# Schematics.net
KiCad netlist of a schematic drawn in Altium Designer
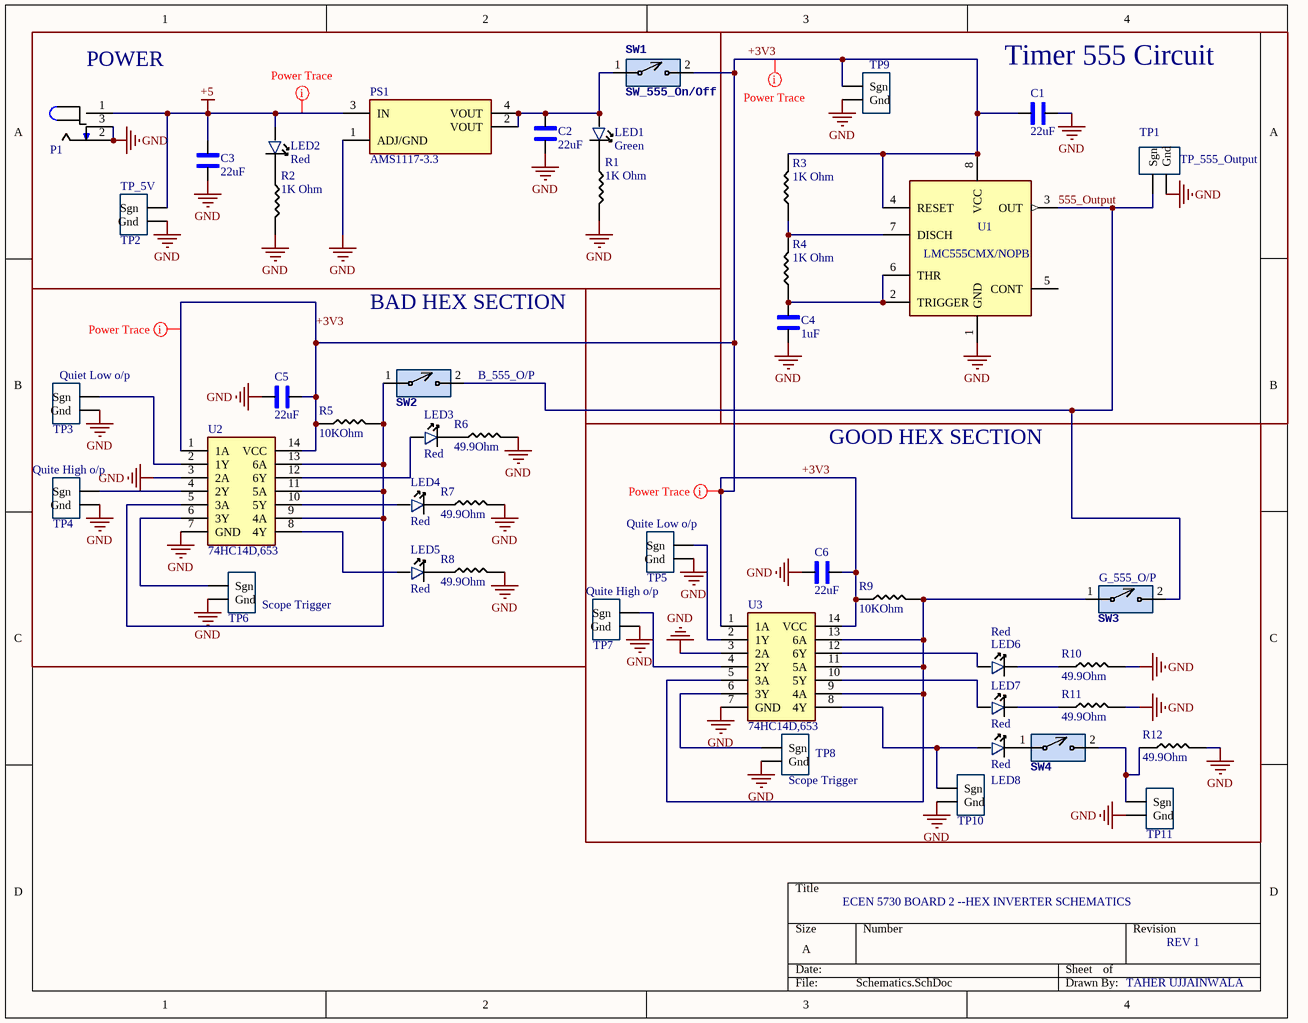
[diagram p0: Schematics.SchDoc]

(export (version "E")
  (design (tool "Eeschema 10.0.6"))
  (components
    (comp (ref "C1")
      (value "22uF")
      (footprint "0805_Passive_Capaciitor")
      (description "MULTILAYER CERAMIC CAPACITORS MLCC - SMD/SMT 22UF 25V 0805 ROHS")
      (fields (field (name "MFR PART #") "CL21A226MAQNNNE") (field (name "LCSC PART#") "C45783"))
      (libsource (lib "ECEN5730Lib_JLC_2021_08") (part "C_22uF_0805"))
    )
    (comp (ref "C2")
      (value "22uF")
      (footprint "0805_Passive_Capaciitor")
      (description "MULTILAYER CERAMIC CAPACITORS MLCC - SMD/SMT 22UF 25V 0805 ROHS")
      (fields (field (name "MFR PART #") "CL21A226MAQNNNE") (field (name "LCSC PART#") "C45783"))
      (libsource (lib "ECEN5730Lib_JLC_2021_08") (part "C_22uF_0805"))
    )
    (comp (ref "C3")
      (value "22uF")
      (footprint "0805_Passive_Capaciitor")
      (description "MULTILAYER CERAMIC CAPACITORS MLCC - SMD/SMT 22UF 25V 0805 ROHS")
      (fields (field (name "MFR PART #") "CL21A226MAQNNNE") (field (name "LCSC PART#") "C45783"))
      (libsource (lib "ECEN5730Lib_JLC_2021_08") (part "C_22uF_0805"))
    )
    (comp (ref "C4")
      (value "1uF")
      (footprint "0402_Passive_Capacitor")
      (description "MULTILAYER CERAMIC CAPACITORS MLCC - SMD/SMT 1UF 25V 0402 ROHS")
      (fields (field (name "MFR PART #") "CL05A105KA5NQNC") (field (name "LCSC PART#") "C52923"))
      (libsource (lib "ECEN5730Lib_JLC_2021_08") (part "C_1uF_0402"))
    )
    (comp (ref "C5")
      (value "22uF")
      (footprint "0805_Passive_Capaciitor")
      (description "MULTILAYER CERAMIC CAPACITORS MLCC - SMD/SMT 22UF 25V 0805 ROHS")
      (fields (field (name "MFR PART #") "CL21A226MAQNNNE") (field (name "LCSC PART#") "C45783"))
      (libsource (lib "ECEN5730Lib_JLC_2021_08") (part "C_22uF_0805"))
    )
    (comp (ref "C6")
      (value "22uF")
      (footprint "0805_Passive_Capaciitor")
      (description "MULTILAYER CERAMIC CAPACITORS MLCC - SMD/SMT 22UF 25V 0805 ROHS")
      (fields (field (name "MFR PART #") "CL21A226MAQNNNE") (field (name "LCSC PART#") "C45783"))
      (libsource (lib "ECEN5730Lib_JLC_2021_08") (part "C_22uF_0805"))
    )
    (comp (ref "LED1")
      (value "Green")
      (footprint "LED_0603")
      (description "LIGHT EMITTING DIODES (LED) GREEN 520~535NM 112~258MCD@20MA TOP VIEW 0603 ROHS")
      (fields (field (name "MFR PART #") "19-217/GHC-YR1S2/3T") (field (name "LCSC PART#") "C72043"))
      (libsource (lib "ECEN5730Lib_JLC_2021_08") (part "LED_GREEN_0603"))
    )
    (comp (ref "LED2")
      (value "Red")
      (footprint "LED_0603")
      (description "LIGHT EMITTING DIODES (LED) RED 520~625NM 90~100MCD@20MA TOP VIEW 0603 ROHS")
      (fields (field (name "MFR PART #") "KT-0603R") (field (name "LCSC PART#") "C2286"))
      (libsource (lib "ECEN5730Lib_JLC_2021_08") (part "LED_RED_0603"))
    )
    (comp (ref "LED3")
      (value "Red")
      (footprint "LED_0603")
      (description "LIGHT EMITTING DIODES (LED) RED 520~625NM 90~100MCD@20MA TOP VIEW 0603 ROHS")
      (fields (field (name "MFR PART #") "KT-0603R") (field (name "LCSC PART#") "C2286"))
      (libsource (lib "ECEN5730Lib_JLC_2021_08") (part "LED_RED_0603"))
    )
    (comp (ref "LED4")
      (value "Red")
      (footprint "LED_0603")
      (description "LIGHT EMITTING DIODES (LED) RED 520~625NM 90~100MCD@20MA TOP VIEW 0603 ROHS")
      (fields (field (name "MFR PART #") "KT-0603R") (field (name "LCSC PART#") "C2286"))
      (libsource (lib "ECEN5730Lib_JLC_2021_08") (part "LED_RED_0603"))
    )
    (comp (ref "LED5")
      (value "Red")
      (footprint "LED_0603")
      (description "LIGHT EMITTING DIODES (LED) RED 520~625NM 90~100MCD@20MA TOP VIEW 0603 ROHS")
      (fields (field (name "MFR PART #") "KT-0603R") (field (name "LCSC PART#") "C2286"))
      (libsource (lib "ECEN5730Lib_JLC_2021_08") (part "LED_RED_0603"))
    )
    (comp (ref "LED6")
      (value "Red")
      (footprint "LED_0603")
      (description "LIGHT EMITTING DIODES (LED) RED 520~625NM 90~100MCD@20MA TOP VIEW 0603 ROHS")
      (fields (field (name "MFR PART #") "KT-0603R") (field (name "LCSC PART#") "C2286"))
      (libsource (lib "ECEN5730Lib_JLC_2021_08") (part "LED_RED_0603"))
    )
    (comp (ref "LED7")
      (value "Red")
      (footprint "LED_0603")
      (description "LIGHT EMITTING DIODES (LED) RED 520~625NM 90~100MCD@20MA TOP VIEW 0603 ROHS")
      (fields (field (name "MFR PART #") "KT-0603R") (field (name "LCSC PART#") "C2286"))
      (libsource (lib "ECEN5730Lib_JLC_2021_08") (part "LED_RED_0603"))
    )
    (comp (ref "LED8")
      (value "Red")
      (footprint "LED_0603")
      (description "LIGHT EMITTING DIODES (LED) RED 520~625NM 90~100MCD@20MA TOP VIEW 0603 ROHS")
      (fields (field (name "MFR PART #") "KT-0603R") (field (name "LCSC PART#") "C2286"))
      (libsource (lib "ECEN5730Lib_JLC_2021_08") (part "LED_RED_0603"))
    )
    (comp (ref "P1")
      (value "Power Jack")
      (footprint "Power_Jack")
      (description "Power Barrel Connector Jack 2.10mm ID (0.083\"), 5.50mm OD (0.217\") Through Hole, Right Angle")
      (fields (field (name "DIGIKEY PART") "CP-102A-ND") (field (name "LCSC PART#") "C136744"))
      (libsource (lib "ECEN5730Lib_JLC_2021_08") (part "P_Power Jack"))
    )
    (comp (ref "PS1")
      (value "AMS1117-3.3")
      (footprint "LDO")
      (description "LOW DROPOUT REGULATORS(LDO) POSITIVE FIXED 1.3V @ 800MA 15V 3.3V 1A SOT-223 ROHS")
      (fields (field (name "LCSC PART#") "C6186"))
      (libsource (lib "ECEN5730Lib_JLC_2021_08") (part "PS_AMS_LDO_3v3"))
    )
    (comp (ref "R1")
      (value "1K Ohm")
      (footprint "0805_Passive_Resistor")
      (description "CHIP RESISTOR - SURFACE MOUNT 1KOHMS ±1% 1/8W 0805 ROHS")
      (fields (field (name "LCSC PART#") "C17513") (field (name "MFR PART #") "0805W8F1001T5E"))
      (libsource (lib "ECEN5730Lib_JLC_2021_08") (part "R_1K_0805"))
    )
    (comp (ref "R2")
      (value "1K Ohm")
      (footprint "0805_Passive_Resistor")
      (description "CHIP RESISTOR - SURFACE MOUNT 1KOHMS ±1% 1/8W 0805 ROHS")
      (fields (field (name "LCSC PART#") "C17513") (field (name "MFR PART #") "0805W8F1001T5E"))
      (libsource (lib "ECEN5730Lib_JLC_2021_08") (part "R_1K_0805"))
    )
    (comp (ref "R3")
      (value "1K Ohm")
      (footprint "0805_Passive_Resistor")
      (description "CHIP RESISTOR - SURFACE MOUNT 1KOHMS ±1% 1/8W 0805 ROHS")
      (fields (field (name "LCSC PART#") "C17513") (field (name "MFR PART #") "0805W8F1001T5E"))
      (libsource (lib "ECEN5730Lib_JLC_2021_08") (part "R_1K_0805"))
    )
    (comp (ref "R4")
      (value "1K Ohm")
      (footprint "0805_Passive_Resistor")
      (description "CHIP RESISTOR - SURFACE MOUNT 1KOHMS ±1% 1/8W 0805 ROHS")
      (fields (field (name "LCSC PART#") "C17513") (field (name "MFR PART #") "0805W8F1001T5E"))
      (libsource (lib "ECEN5730Lib_JLC_2021_08") (part "R_1K_0805"))
    )
    (comp (ref "R5")
      (value "10KOhm")
      (footprint "0402_Passive_Resistor")
      (description "CHIP RESISTOR - SURFACE MOUNT 10KOHMS ±1% 1/16W 0402 ROHS")
      (fields (field (name "MFR PART #") "0402WGF1002TCE") (field (name "LCSC PART#") "C25744"))
      (libsource (lib "ECEN5730Lib_JLC_2021_08") (part "R_10KOhm_0402"))
    )
    (comp (ref "R6")
      (value "49.9Ohm")
      (footprint "0402_Passive_Resistor")
      (description "CHIP RESISTOR - SURFACE MOUNT 49.9OHMS ±1% 1/16W 0402 ROHS")
      (fields (field (name "MFR PART #") "0402WGF499JTCE") (field (name "LCSC PART#") "C25120"))
      (libsource (lib "ECEN5730Lib_JLC_2021_08") (part "R_50Ohm_0402"))
    )
    (comp (ref "R7")
      (value "49.9Ohm")
      (footprint "0402_Passive_Resistor")
      (description "CHIP RESISTOR - SURFACE MOUNT 49.9OHMS ±1% 1/16W 0402 ROHS")
      (fields (field (name "MFR PART #") "0402WGF499JTCE") (field (name "LCSC PART#") "C25120"))
      (libsource (lib "ECEN5730Lib_JLC_2021_08") (part "R_50Ohm_0402"))
    )
    (comp (ref "R8")
      (value "49.9Ohm")
      (footprint "0402_Passive_Resistor")
      (description "CHIP RESISTOR - SURFACE MOUNT 49.9OHMS ±1% 1/16W 0402 ROHS")
      (fields (field (name "MFR PART #") "0402WGF499JTCE") (field (name "LCSC PART#") "C25120"))
      (libsource (lib "ECEN5730Lib_JLC_2021_08") (part "R_50Ohm_0402"))
    )
    (comp (ref "R9")
      (value "10KOhm")
      (footprint "0402_Passive_Resistor")
      (description "CHIP RESISTOR - SURFACE MOUNT 10KOHMS ±1% 1/16W 0402 ROHS")
      (fields (field (name "MFR PART #") "0402WGF1002TCE") (field (name "LCSC PART#") "C25744"))
      (libsource (lib "ECEN5730Lib_JLC_2021_08") (part "R_10KOhm_0402"))
    )
    (comp (ref "R10")
      (value "49.9Ohm")
      (footprint "0402_Passive_Resistor")
      (description "CHIP RESISTOR - SURFACE MOUNT 49.9OHMS ±1% 1/16W 0402 ROHS")
      (fields (field (name "MFR PART #") "0402WGF499JTCE") (field (name "LCSC PART#") "C25120"))
      (libsource (lib "ECEN5730Lib_JLC_2021_08") (part "R_50Ohm_0402"))
    )
    (comp (ref "R11")
      (value "49.9Ohm")
      (footprint "0402_Passive_Resistor")
      (description "CHIP RESISTOR - SURFACE MOUNT 49.9OHMS ±1% 1/16W 0402 ROHS")
      (fields (field (name "MFR PART #") "0402WGF499JTCE") (field (name "LCSC PART#") "C25120"))
      (libsource (lib "ECEN5730Lib_JLC_2021_08") (part "R_50Ohm_0402"))
    )
    (comp (ref "R12")
      (value "49.9Ohm")
      (footprint "0402_Passive_Resistor")
      (description "CHIP RESISTOR - SURFACE MOUNT 49.9OHMS ±1% 1/16W 0402 ROHS")
      (fields (field (name "MFR PART #") "0402WGF499JTCE") (field (name "LCSC PART#") "C25120"))
      (libsource (lib "ECEN5730Lib_JLC_2021_08") (part "R_50Ohm_0402"))
    )
    (comp (ref "SW1")
      (value "SW_555_On/Off")
      (footprint "2Pin-Header-Conn")
      (description "2Pin Header")
      (fields (field (name "LCSC PART#") "C124375"))
      (libsource (lib "ECEN5730Lib_JLC_2021_08") (part "SW_2Pin_100mil_Switch"))
    )
    (comp (ref "SW2")
      (value "SW_2Pin_100mil_Switch")
      (footprint "2Pin-Header-Conn")
      (description "2Pin Header")
      (fields (field (name "LCSC PART#") "C124375"))
      (libsource (lib "ECEN5730Lib_JLC_2021_08") (part "SW_2Pin_100mil_Switch"))
    )
    (comp (ref "SW3")
      (value "SW_2Pin_100mil_Switch")
      (footprint "2Pin-Header-Conn")
      (description "2Pin Header")
      (fields (field (name "LCSC PART#") "C124375"))
      (libsource (lib "ECEN5730Lib_JLC_2021_08") (part "SW_2Pin_100mil_Switch"))
    )
    (comp (ref "SW4")
      (value "SW_2Pin_100mil_Switch")
      (footprint "2Pin-Header-Conn")
      (description "2Pin Header")
      (fields (field (name "LCSC PART#") "C124375"))
      (libsource (lib "ECEN5730Lib_JLC_2021_08") (part "SW_2Pin_100mil_Switch"))
    )
    (comp (ref "TP1")
      (value "TP_555_Output")
      (footprint "TP10x_Probe")
      (description "Test Point 300 mil centers")
      (libsource (lib "") (part "TP_10x_Probe_2"))
    )
    (comp (ref "TP2")
      (value "TP_5V")
      (footprint "TP10x_Probe")
      (description "Test Point 300 mil centers")
      (libsource (lib "ECEN5730Lib_Manual_2021_08") (part "TP_10x_Probe"))
    )
    (comp (ref "TP3")
      (value "10x Probe TP")
      (footprint "TP10x_Probe")
      (description "Test Point 300 mil centers")
      (libsource (lib "ECEN5730Lib_Manual_2021_08") (part "TP_10x_Probe"))
    )
    (comp (ref "TP4")
      (value "10x Probe TP")
      (footprint "TP10x_Probe")
      (description "Test Point 300 mil centers")
      (libsource (lib "ECEN5730Lib_Manual_2021_08") (part "TP_10x_Probe"))
    )
    (comp (ref "TP5")
      (value "10x Probe TP")
      (footprint "TP10x_Probe")
      (description "Test Point 300 mil centers")
      (libsource (lib "ECEN5730Lib_Manual_2021_08") (part "TP_10x_Probe"))
    )
    (comp (ref "TP6")
      (value "10x Probe TP")
      (footprint "TP10x_Probe")
      (description "Test Point 300 mil centers")
      (libsource (lib "") (part "TP_10x_Probe_1"))
    )
    (comp (ref "TP7")
      (value "10x Probe TP")
      (footprint "TP10x_Probe")
      (description "Test Point 300 mil centers")
      (libsource (lib "ECEN5730Lib_Manual_2021_08") (part "TP_10x_Probe"))
    )
    (comp (ref "TP8")
      (value "10x Probe TP")
      (footprint "TP10x_Probe")
      (description "Test Point 300 mil centers")
      (libsource (lib "") (part "TP_10x_Probe_1"))
    )
    (comp (ref "TP9")
      (value "10x Probe TP")
      (footprint "TP10x_Probe")
      (description "Test Point 300 mil centers")
      (libsource (lib "") (part "TP_10x_Probe_1"))
    )
    (comp (ref "TP10")
      (value "10x Probe TP")
      (footprint "TP10x_Probe")
      (description "Test Point 300 mil centers")
      (libsource (lib "") (part "TP_10x_Probe_1"))
    )
    (comp (ref "TP11")
      (value "10x Probe TP")
      (footprint "TP10x_Probe")
      (description "Test Point 300 mil centers")
      (libsource (lib "") (part "TP_10x_Probe_1"))
    )
    (comp (ref "U1")
      (value "LMC555CMX/NOPB")
      (footprint "TS555IDTTR")
      (description "555 Type, Timer/Oscillator _Single_ IC 3MHz 8-SO")
      (fields (field (name "LCSC PART#") "C90760"))
      (libsource (lib "ECEN5730Lib_JLC_2021_08") (part "U_555_Fast"))
    )
    (comp (ref "U2")
      (value "74HC14D,653")
      (footprint "HEX_74AC14")
      (description "Inverter IC 6 Channel Schmitt Trigger 14-SOIC")
      (fields (field (name "LCSC PART#") "C5605"))
      (libsource (lib "ECEN5730Lib_JLC_2021_08") (part "U_7414_HC_Hex"))
    )
    (comp (ref "U3")
      (value "74HC14D,653")
      (footprint "HEX_74AC14")
      (description "Inverter IC 6 Channel Schmitt Trigger 14-SOIC")
      (fields (field (name "LCSC PART#") "C5605"))
      (libsource (lib "ECEN5730Lib_JLC_2021_08") (part "U_7414_HC_Hex"))
    )
  )
  (nets
    (net (code "1") (name "+5") (class "Default")
      (node (ref "C3") (pin "2") (pinfunction "2_2") (pintype "passive"))
      (node (ref "LED2") (pin "1") (pinfunction "1_1") (pintype "passive"))
      (node (ref "P1") (pin "1") (pinfunction "1_1") (pintype "power_in"))
      (node (ref "PS1") (pin "3") (pinfunction "IN_3") (pintype "power_in"))
      (node (ref "TP2") (pin "1") (pinfunction "Sgn_1") (pintype "passive"))
    )
    (net (code "2") (name "/+3V3") (class "Default")
      (node (ref "C1") (pin "1") (pinfunction "1_1") (pintype "passive"))
      (node (ref "C5") (pin "1") (pinfunction "1_1") (pintype "passive"))
      (node (ref "C6") (pin "1") (pinfunction "1_1") (pintype "passive"))
      (node (ref "R3") (pin "2") (pinfunction "2_2") (pintype "passive"))
      (node (ref "R5") (pin "1") (pinfunction "1_1") (pintype "passive"))
      (node (ref "R9") (pin "1") (pinfunction "1_1") (pintype "passive"))
      (node (ref "SW1") (pin "2") (pinfunction "2_2") (pintype "passive"))
      (node (ref "TP9") (pin "1") (pinfunction "Sgn_1") (pintype "passive"))
      (node (ref "U1") (pin "4") (pinfunction "RESET_4") (pintype "passive"))
      (node (ref "U1") (pin "8") (pinfunction "VCC_8") (pintype "power_in"))
      (node (ref "U2") (pin "1") (pinfunction "1A_1") (pintype "passive"))
      (node (ref "U2") (pin "14") (pinfunction "VCC_14") (pintype "passive"))
      (node (ref "U3") (pin "1") (pinfunction "1A_1") (pintype "passive"))
      (node (ref "U3") (pin "14") (pinfunction "VCC_14") (pintype "passive"))
    )
    (net (code "3") (name "/555_Output") (class "Default")
      (node (ref "SW2") (pin "2") (pinfunction "2_2") (pintype "passive"))
      (node (ref "SW3") (pin "2") (pinfunction "2_2") (pintype "passive"))
      (node (ref "TP1") (pin "1") (pinfunction "Sgn_1") (pintype "passive"))
      (node (ref "U1") (pin "3") (pinfunction "OUT_3") (pintype "output"))
    )
    (net (code "4") (name "GND") (class "Default")
      (node (ref "C1") (pin "2") (pinfunction "2_2") (pintype "passive"))
      (node (ref "C2") (pin "1") (pinfunction "1_1") (pintype "passive"))
      (node (ref "C3") (pin "1") (pinfunction "1_1") (pintype "passive"))
      (node (ref "C4") (pin "1") (pinfunction "1_1") (pintype "passive"))
      (node (ref "C5") (pin "2") (pinfunction "2_2") (pintype "passive"))
      (node (ref "C6") (pin "2") (pinfunction "2_2") (pintype "passive"))
      (node (ref "P1") (pin "2") (pinfunction "2_2") (pintype "power_in"))
      (node (ref "P1") (pin "3") (pinfunction "3_3") (pintype "power_in"))
      (node (ref "PS1") (pin "1") (pinfunction "ADJ/GND_1") (pintype "passive"))
      (node (ref "R1") (pin "2") (pinfunction "2_2") (pintype "passive"))
      (node (ref "R10") (pin "2") (pinfunction "2_2") (pintype "passive"))
      (node (ref "R11") (pin "2") (pinfunction "2_2") (pintype "passive"))
      (node (ref "R12") (pin "2") (pinfunction "2_2") (pintype "passive"))
      (node (ref "R2") (pin "2") (pinfunction "2_2") (pintype "passive"))
      (node (ref "R6") (pin "2") (pinfunction "2_2") (pintype "passive"))
      (node (ref "R7") (pin "2") (pinfunction "2_2") (pintype "passive"))
      (node (ref "R8") (pin "2") (pinfunction "2_2") (pintype "passive"))
      (node (ref "TP1") (pin "2") (pinfunction "Gnd_2") (pintype "passive"))
      (node (ref "TP10") (pin "2") (pinfunction "Gnd_2") (pintype "passive"))
      (node (ref "TP11") (pin "2") (pinfunction "Gnd_2") (pintype "passive"))
      (node (ref "TP2") (pin "2") (pinfunction "Gnd_2") (pintype "passive"))
      (node (ref "TP3") (pin "2") (pinfunction "Gnd_2") (pintype "passive"))
      (node (ref "TP4") (pin "2") (pinfunction "Gnd_2") (pintype "passive"))
      (node (ref "TP5") (pin "2") (pinfunction "Gnd_2") (pintype "passive"))
      (node (ref "TP6") (pin "2") (pinfunction "Gnd_2") (pintype "passive"))
      (node (ref "TP7") (pin "2") (pinfunction "Gnd_2") (pintype "passive"))
      (node (ref "TP8") (pin "2") (pinfunction "Gnd_2") (pintype "passive"))
      (node (ref "TP9") (pin "2") (pinfunction "Gnd_2") (pintype "passive"))
      (node (ref "U1") (pin "1") (pinfunction "GND_1") (pintype "power_in"))
      (node (ref "U2") (pin "3") (pinfunction "2A_3") (pintype "passive"))
      (node (ref "U2") (pin "7") (pinfunction "GND_7") (pintype "passive"))
      (node (ref "U3") (pin "3") (pinfunction "2A_3") (pintype "passive"))
      (node (ref "U3") (pin "7") (pinfunction "GND_7") (pintype "passive"))
    )
    (net (code "5") (name "Net-(C2-Pad2)") (class "Default")
      (node (ref "C2") (pin "2") (pinfunction "2_2") (pintype "passive"))
      (node (ref "LED1") (pin "1") (pinfunction "1_1") (pintype "passive"))
      (node (ref "PS1") (pin "2") (pinfunction "VOUT_2") (pintype "power_in"))
      (node (ref "PS1") (pin "4") (pinfunction "VOUT_4") (pintype "power_in"))
      (node (ref "SW1") (pin "1") (pinfunction "1_1") (pintype "passive"))
    )
    (net (code "6") (name "Net-(LED1-Pad2)") (class "Default")
      (node (ref "LED1") (pin "2") (pinfunction "2_2") (pintype "passive"))
      (node (ref "R1") (pin "1") (pinfunction "1_1") (pintype "passive"))
    )
    (net (code "7") (name "Net-(LED2-Pad2)") (class "Default")
      (node (ref "LED2") (pin "2") (pinfunction "2_2") (pintype "passive"))
      (node (ref "R2") (pin "1") (pinfunction "1_1") (pintype "passive"))
    )
    (net (code "8") (name "Net-(LED3-Pad2)") (class "Default")
      (node (ref "LED3") (pin "2") (pinfunction "2_2") (pintype "passive"))
      (node (ref "R6") (pin "1") (pinfunction "1_1") (pintype "passive"))
    )
    (net (code "9") (name "Net-(LED4-Pad2)") (class "Default")
      (node (ref "LED4") (pin "2") (pinfunction "2_2") (pintype "passive"))
      (node (ref "R7") (pin "1") (pinfunction "1_1") (pintype "passive"))
    )
    (net (code "10") (name "Net-(LED5-Pad2)") (class "Default")
      (node (ref "LED5") (pin "2") (pinfunction "2_2") (pintype "passive"))
      (node (ref "R8") (pin "1") (pinfunction "1_1") (pintype "passive"))
    )
    (net (code "11") (name "Net-(LED6-Pad2)") (class "Default")
      (node (ref "LED6") (pin "2") (pinfunction "2_2") (pintype "passive"))
      (node (ref "R10") (pin "1") (pinfunction "1_1") (pintype "passive"))
    )
    (net (code "12") (name "Net-(LED7-Pad2)") (class "Default")
      (node (ref "LED7") (pin "2") (pinfunction "2_2") (pintype "passive"))
      (node (ref "R11") (pin "1") (pinfunction "1_1") (pintype "passive"))
    )
    (net (code "13") (name "Net-(LED8-Pad2)") (class "Default")
      (node (ref "LED8") (pin "2") (pinfunction "2_2") (pintype "passive"))
      (node (ref "SW4") (pin "1") (pinfunction "1_1") (pintype "passive"))
    )
    (net (code "14") (name "Net-(TP3-Sgn)") (class "Default")
      (node (ref "TP3") (pin "1") (pinfunction "Sgn_1") (pintype "passive"))
      (node (ref "U2") (pin "2") (pinfunction "1Y_2") (pintype "passive"))
    )
    (net (code "15") (name "Net-(TP4-Sgn)") (class "Default")
      (node (ref "TP4") (pin "1") (pinfunction "Sgn_1") (pintype "passive"))
      (node (ref "U2") (pin "4") (pinfunction "2Y_4") (pintype "passive"))
    )
    (net (code "16") (name "Net-(TP5-Sgn)") (class "Default")
      (node (ref "TP5") (pin "1") (pinfunction "Sgn_1") (pintype "passive"))
      (node (ref "U3") (pin "2") (pinfunction "1Y_2") (pintype "passive"))
    )
    (net (code "17") (name "Net-(TP6-Sgn)") (class "Default")
      (node (ref "TP6") (pin "1") (pinfunction "Sgn_1") (pintype "passive"))
      (node (ref "U2") (pin "6") (pinfunction "3Y_6") (pintype "passive"))
    )
    (net (code "18") (name "Net-(TP7-Sgn)") (class "Default")
      (node (ref "TP7") (pin "1") (pinfunction "Sgn_1") (pintype "passive"))
      (node (ref "U3") (pin "4") (pinfunction "2Y_4") (pintype "passive"))
    )
    (net (code "19") (name "Net-(TP8-Sgn)") (class "Default")
      (node (ref "TP8") (pin "1") (pinfunction "Sgn_1") (pintype "passive"))
      (node (ref "U3") (pin "6") (pinfunction "3Y_6") (pintype "passive"))
    )
    (net (code "20") (name "Net-(TP10-Sgn)") (class "Default")
      (node (ref "LED8") (pin "1") (pinfunction "1_1") (pintype "passive"))
      (node (ref "TP10") (pin "1") (pinfunction "Sgn_1") (pintype "passive"))
      (node (ref "U3") (pin "8") (pinfunction "4Y_8") (pintype "passive"))
    )
    (net (code "21") (name "Net-(TP11-Sgn)") (class "Default")
      (node (ref "R12") (pin "1") (pinfunction "1_1") (pintype "passive"))
      (node (ref "SW4") (pin "2") (pinfunction "2_2") (pintype "passive"))
      (node (ref "TP11") (pin "1") (pinfunction "Sgn_1") (pintype "passive"))
    )
    (net (code "22") (name "Net-(U1-DISCH)") (class "Default")
      (node (ref "R3") (pin "1") (pinfunction "1_1") (pintype "passive"))
      (node (ref "R4") (pin "2") (pinfunction "2_2") (pintype "passive"))
      (node (ref "U1") (pin "7") (pinfunction "DISCH_7") (pintype "passive"))
    )
    (net (code "23") (name "Net-(U1-THR)") (class "Default")
      (node (ref "C4") (pin "2") (pinfunction "2_2") (pintype "passive"))
      (node (ref "R4") (pin "1") (pinfunction "1_1") (pintype "passive"))
      (node (ref "U1") (pin "2") (pinfunction "TRIGGER_2") (pintype "passive"))
      (node (ref "U1") (pin "6") (pinfunction "THR_6") (pintype "passive"))
    )
    (net (code "24") (name "Net-(U2-3A)") (class "Default")
      (node (ref "R5") (pin "2") (pinfunction "2_2") (pintype "passive"))
      (node (ref "SW2") (pin "1") (pinfunction "1_1") (pintype "passive"))
      (node (ref "U2") (pin "11") (pinfunction "5A_11") (pintype "passive"))
      (node (ref "U2") (pin "13") (pinfunction "6A_13") (pintype "passive"))
      (node (ref "U2") (pin "5") (pinfunction "3A_5") (pintype "passive"))
      (node (ref "U2") (pin "9") (pinfunction "4A_9") (pintype "passive"))
    )
    (net (code "25") (name "Net-(U2-4Y)") (class "Default")
      (node (ref "LED5") (pin "1") (pinfunction "1_1") (pintype "passive"))
      (node (ref "U2") (pin "8") (pinfunction "4Y_8") (pintype "passive"))
    )
    (net (code "26") (name "Net-(U2-5Y)") (class "Default")
      (node (ref "LED4") (pin "1") (pinfunction "1_1") (pintype "passive"))
      (node (ref "U2") (pin "10") (pinfunction "5Y_10") (pintype "passive"))
    )
    (net (code "27") (name "Net-(U2-6Y)") (class "Default")
      (node (ref "LED3") (pin "1") (pinfunction "1_1") (pintype "passive"))
      (node (ref "U2") (pin "12") (pinfunction "6Y_12") (pintype "passive"))
    )
    (net (code "28") (name "Net-(U3-3A)") (class "Default")
      (node (ref "R9") (pin "2") (pinfunction "2_2") (pintype "passive"))
      (node (ref "SW3") (pin "1") (pinfunction "1_1") (pintype "passive"))
      (node (ref "U3") (pin "11") (pinfunction "5A_11") (pintype "passive"))
      (node (ref "U3") (pin "13") (pinfunction "6A_13") (pintype "passive"))
      (node (ref "U3") (pin "5") (pinfunction "3A_5") (pintype "passive"))
      (node (ref "U3") (pin "9") (pinfunction "4A_9") (pintype "passive"))
    )
    (net (code "29") (name "Net-(U3-5Y)") (class "Default")
      (node (ref "LED7") (pin "1") (pinfunction "1_1") (pintype "passive"))
      (node (ref "U3") (pin "10") (pinfunction "5Y_10") (pintype "passive"))
    )
    (net (code "30") (name "Net-(U3-6Y)") (class "Default")
      (node (ref "LED6") (pin "1") (pinfunction "1_1") (pintype "passive"))
      (node (ref "U3") (pin "12") (pinfunction "6Y_12") (pintype "passive"))
    )
    (net (code "31") (name "unconnected-(U1-CONT-Pad5)") (class "Default")
      (node (ref "U1") (pin "5") (pinfunction "CONT_5") (pintype "passive"))
    )
  )
)
